# Schematic_new_submission.net
KiCad netlist of a schematic drawn in Altium Designer
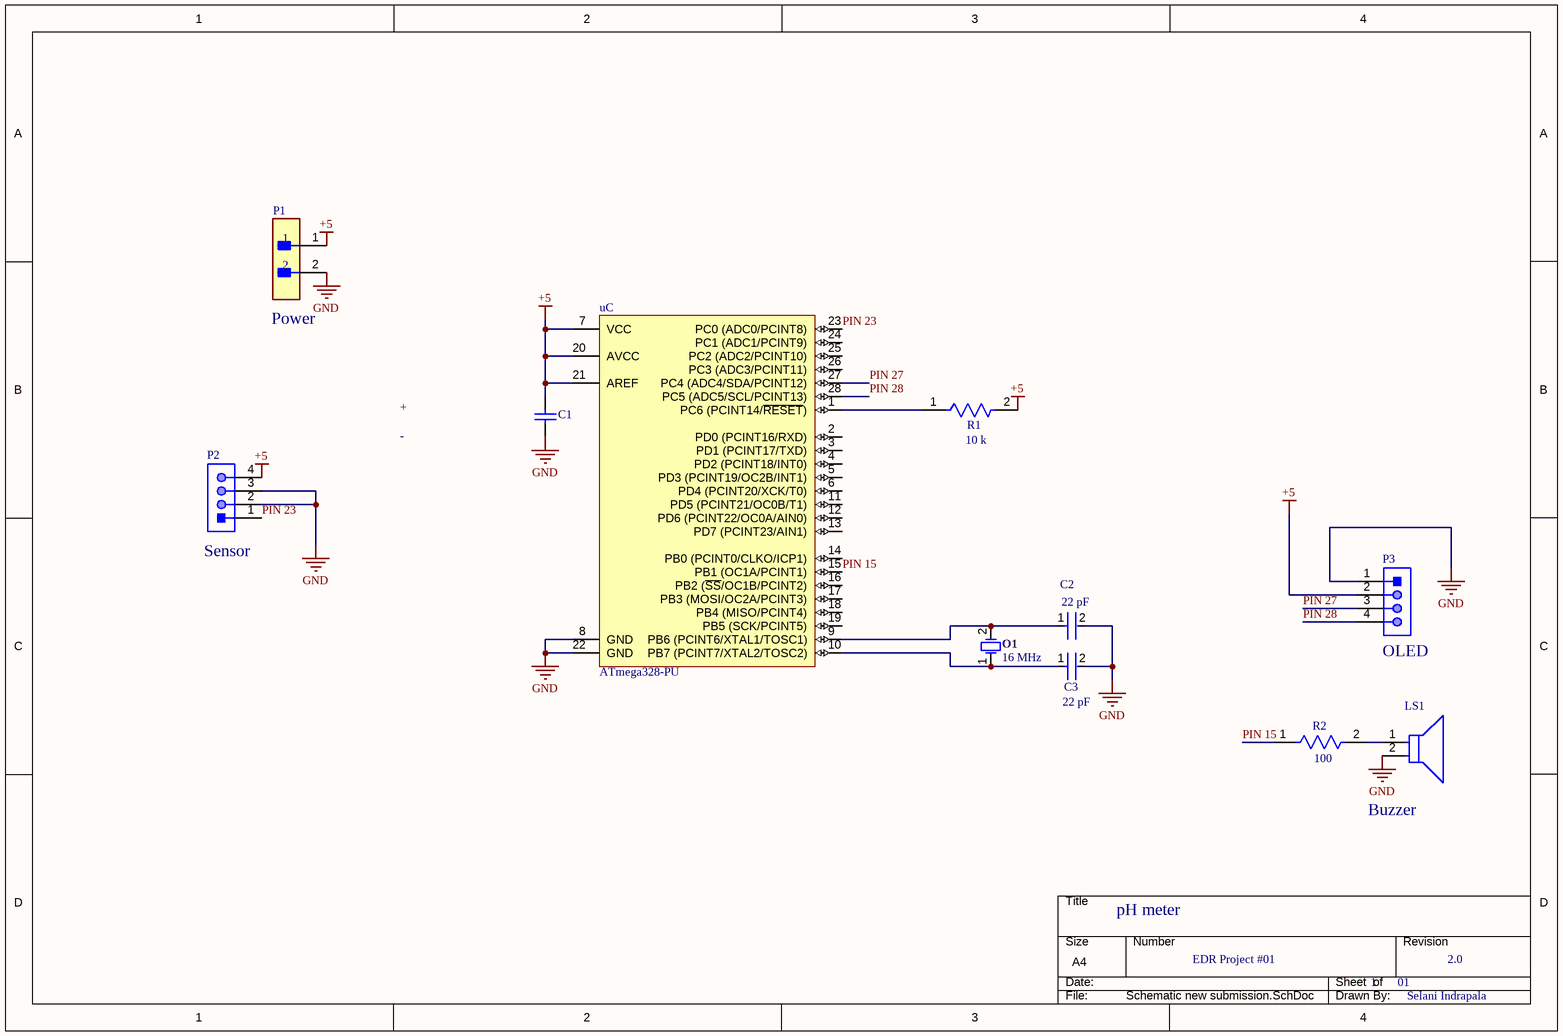
[diagram p0: Schematic new submission.SchDoc]

(export (version "E")
  (design (tool "Eeschema 10.0.6"))
  (components
    (comp (ref "C1")
      (value "MD015E104MAB")
      (footprint "AVX-MD01")
      (description "Ceramic Capacitor, 0.1 uF, +/- 20%, 50 V, -55 to 125 degC, 2-Pin THD (MD01), Bulk")
      (fields (field (name "MANUFACTURER") "AVX"))
      (libsource (lib "Altium Content Vault") (part "CAP-NP-2"))
    )
    (comp (ref "C2")
      (value "RCE5C1H220J0M1H03A")
      (footprint "FP-RCE0K1-MFG")
      (description "Cap Ceramic 22pF 50V C0G ±5% Radial 5mm +125°C Automotive Bulk")
      (fields (field (name "TOLERANCE") "5%"))
      (libsource (lib "Altium Content Vault") (part "b4654b650e69147ec39a6b967a45e02"))
    )
    (comp (ref "C3")
      (value "RCE5C1H220J0M1H03A")
      (footprint "FP-RCE0K1-MFG")
      (description "Cap Ceramic 22pF 50V C0G ±5% Radial 5mm +125°C Automotive Bulk")
      (fields (field (name "TOLERANCE") "5%"))
      (libsource (lib "Altium Content Vault") (part "b4654b650e69147ec39a6b967a45e02"))
    )
    (comp (ref "LS1")
      (value "PS1720P02")
      (footprint "FP-PS1720P02-MFG")
      (description "Audio Buzzer Piezo 3Vo-p Pin Through Hole")
      (fields (field (name "OCTOPART") "https://octopart.com/ps1720p02-tdk-154429"))
      (libsource (lib "Altium Content Vault") (part "5f581d31613f872430949aa526fd155"))
    )
    (comp (ref "O1")
      (value "FOXSLF/160-20")
      (footprint "FOX-FOXSLF160-20")
      (description "Resistance Weld Thru-Hole Crystal, 16 MHz, -20 to 70 degC, 2-Pin THD, RoHS, Bulk")
      (fields (field (name "TOLERANCE") "1%"))
      (libsource (lib "Altium Content Vault") (part "XTAL-1-2-2"))
    )
    (comp (ref "P1")
      (value "M20-9990246")
      (footprint "FP-M20-9990246-MFG")
      (description "CONN HEADER VERT 2POS 2.54MM")
      (fields
        (field (name "OCTOPART") "https://octopart.com/m20-9990246-harwin-2590635")
        (field (name "MANUFACTURER") "Harwin")
      )
      (libsource (lib "Altium Content Vault") (part "3bc925449376181038e59eaffc5286c"))
    )
    (comp (ref "P2")
      (value "Sensor")
      (footprint "61900411121")
      (description "Male Locking Header WR-WTB, THT, Vertical, pitch 2.54 mm, 1 x 4 position")
      (fields
        (field (name "MANUFACTURER") "Wurth Elektronik")
        (field (name "PART NUMBER") "61900411121")
        (field (name "PUBLISHER") "WurthElektronik")
      )
      (libsource (lib "") (part "WE-CN-1P-M-R4_1"))
    )
    (comp (ref "P3")
      (value "OLED")
      (footprint "61900411121")
      (description "Male Locking Header WR-WTB, THT, Vertical, pitch 2.54 mm, 1 x 4 position")
      (fields
        (field (name "MANUFACTURER") "Wurth Elektronik")
        (field (name "PART NUMBER") "61900411121")
        (field (name "PUBLISHER") "WurthElektronik")
      )
      (libsource (lib "Altium Content Vault") (part "WE-CN-1P-M-R4"))
    )
    (comp (ref "R1")
      (value "MBB02070C1002FCT00")
      (footprint "FP-MBB0207-MFG")
      (description "RES 10K OHM 0.6W 1% AXIAL")
      (fields (field (name "TOLERANCE") "1%"))
      (libsource (lib "Altium Content Vault") (part "1029c3af85768c4190bb7ad29bc67b5"))
    )
    (comp (ref "R2")
      (value "RG1005P-101-B-T5")
      (footprint "FP-RG1005-IPC_B")
      (description "Automotive Metal Thin Film Chip Resistor, 0402, 100Ω, 0.1%, 25ppm/°C, 0.0625W, 75V")
      (fields (field (name "TOLERANCE") "0.1%"))
      (libsource (lib "Altium Content Vault") (part "1029c3af85768c4190bb7ad29bc67b5"))
    )
    (comp (ref "uC")
      (value "ATmega328-PU")
      (footprint "28P3")
      (libsource (lib "Altium Content Vault") (part "MC-8B-ATM48-IL28"))
    )
  )
  (nets
    (net (code "1") (name "+5") (class "Default")
      (node (ref "C1") (pin "2") (pinfunction "2_2") (pintype "passive"))
      (node (ref "P1") (pin "1") (pinfunction "1_1") (pintype "passive"))
      (node (ref "P2") (pin "4") (pinfunction "4_4") (pintype "passive"))
      (node (ref "P3") (pin "2") (pinfunction "2_2") (pintype "passive"))
      (node (ref "R1") (pin "2") (pinfunction "2_2") (pintype "passive"))
      (node (ref "uC") (pin "20") (pinfunction "AVCC_20") (pintype "power_in"))
      (node (ref "uC") (pin "21") (pinfunction "AREF_21") (pintype "power_in"))
      (node (ref "uC") (pin "7") (pinfunction "VCC_7") (pintype "power_in"))
    )
    (net (code "2") (name "/PIN 15") (class "Default")
      (node (ref "R2") (pin "1") (pinfunction "1_1") (pintype "passive"))
      (node (ref "uC") (pin "15") (pinfunction "PB1_(OC1A/PCINT1)_15") (pintype "bidirectional"))
    )
    (net (code "3") (name "/PIN 23") (class "Default")
      (node (ref "P2") (pin "1") (pinfunction "1_1") (pintype "passive"))
      (node (ref "uC") (pin "23") (pinfunction "PC0_(ADC0/PCINT8)_23") (pintype "bidirectional"))
    )
    (net (code "4") (name "/PIN 27") (class "Default")
      (node (ref "P3") (pin "3") (pinfunction "3_3") (pintype "passive"))
      (node (ref "uC") (pin "27") (pinfunction "PC4_(ADC4/SDA/PCINT12)_27") (pintype "bidirectional"))
    )
    (net (code "5") (name "/PIN 28") (class "Default")
      (node (ref "P3") (pin "4") (pinfunction "4_4") (pintype "passive"))
      (node (ref "uC") (pin "28") (pinfunction "PC5_(ADC5/SCL/PCINT13)_28") (pintype "bidirectional"))
    )
    (net (code "6") (name "GND") (class "Default")
      (node (ref "C1") (pin "1") (pinfunction "1_1") (pintype "passive"))
      (node (ref "C2") (pin "2") (pinfunction "2_2") (pintype "passive"))
      (node (ref "C3") (pin "2") (pinfunction "2_2") (pintype "passive"))
      (node (ref "LS1") (pin "2") (pinfunction "2_2") (pintype "passive"))
      (node (ref "P1") (pin "2") (pinfunction "2_2") (pintype "passive"))
      (node (ref "P2") (pin "2") (pinfunction "2_2") (pintype "passive"))
      (node (ref "P2") (pin "3") (pinfunction "3_3") (pintype "passive"))
      (node (ref "P3") (pin "1") (pinfunction "1_1") (pintype "passive"))
      (node (ref "uC") (pin "22") (pinfunction "GND_22") (pintype "power_in"))
      (node (ref "uC") (pin "8") (pinfunction "GND_8") (pintype "power_in"))
    )
    (net (code "7") (name "Net-(LS1-Pad1)") (class "Default")
      (node (ref "LS1") (pin "1") (pinfunction "1_1") (pintype "passive"))
      (node (ref "R2") (pin "2") (pinfunction "2_2") (pintype "passive"))
    )
    (net (code "8") (name "Net-(uC-PB6_(PCINT6{slash}XTAL1{slash}TOSC1))") (class "Default")
      (node (ref "C2") (pin "1") (pinfunction "1_1") (pintype "passive"))
      (node (ref "O1") (pin "2") (pinfunction "2_2") (pintype "passive"))
      (node (ref "uC") (pin "9") (pinfunction "PB6_(PCINT6/XTAL1/TOSC1)_9") (pintype "bidirectional"))
    )
    (net (code "9") (name "Net-(uC-PB7_(PCINT7{slash}XTAL2{slash}TOSC2))") (class "Default")
      (node (ref "C3") (pin "1") (pinfunction "1_1") (pintype "passive"))
      (node (ref "O1") (pin "1") (pinfunction "1_1") (pintype "passive"))
      (node (ref "uC") (pin "10") (pinfunction "PB7_(PCINT7/XTAL2/TOSC2)_10") (pintype "bidirectional"))
    )
    (net (code "10") (name "Net-(uC-PC6_(PCINT14{slash}~{RESET}))") (class "Default")
      (node (ref "R1") (pin "1") (pinfunction "1_1") (pintype "passive"))
      (node (ref "uC") (pin "1") (pinfunction "PC6_(PCINT14/~{RESET})_1") (pintype "bidirectional"))
    )
    (net (code "11") (name "unconnected-(uC-PB0_(PCINT0{slash}CLKO{slash}ICP1)-Pad14)") (class "Default")
      (node (ref "uC") (pin "14") (pinfunction "PB0_(PCINT0/CLKO/ICP1)_14") (pintype "bidirectional"))
    )
    (net (code "12") (name "unconnected-(uC-PB2_(~{SS}{slash}OC1B{slash}PCINT2)-Pad16)") (class "Default")
      (node (ref "uC") (pin "16") (pinfunction "PB2_(~{SS}/OC1B/PCINT2)_16") (pintype "bidirectional"))
    )
    (net (code "13") (name "unconnected-(uC-PB3_(MOSI{slash}OC2A{slash}PCINT3)-Pad17)") (class "Default")
      (node (ref "uC") (pin "17") (pinfunction "PB3_(MOSI/OC2A/PCINT3)_17") (pintype "bidirectional"))
    )
    (net (code "14") (name "unconnected-(uC-PB4_(MISO{slash}PCINT4)-Pad18)") (class "Default")
      (node (ref "uC") (pin "18") (pinfunction "PB4_(MISO/PCINT4)_18") (pintype "bidirectional"))
    )
    (net (code "15") (name "unconnected-(uC-PB5_(SCK{slash}PCINT5)-Pad19)") (class "Default")
      (node (ref "uC") (pin "19") (pinfunction "PB5_(SCK/PCINT5)_19") (pintype "bidirectional"))
    )
    (net (code "16") (name "unconnected-(uC-PC1_(ADC1{slash}PCINT9)-Pad24)") (class "Default")
      (node (ref "uC") (pin "24") (pinfunction "PC1_(ADC1/PCINT9)_24") (pintype "bidirectional"))
    )
    (net (code "17") (name "unconnected-(uC-PC2_(ADC2{slash}PCINT10)-Pad25)") (class "Default")
      (node (ref "uC") (pin "25") (pinfunction "PC2_(ADC2/PCINT10)_25") (pintype "bidirectional"))
    )
    (net (code "18") (name "unconnected-(uC-PC3_(ADC3{slash}PCINT11)-Pad26)") (class "Default")
      (node (ref "uC") (pin "26") (pinfunction "PC3_(ADC3/PCINT11)_26") (pintype "bidirectional"))
    )
    (net (code "19") (name "unconnected-(uC-PD0_(PCINT16{slash}RXD)-Pad2)") (class "Default")
      (node (ref "uC") (pin "2") (pinfunction "PD0_(PCINT16/RXD)_2") (pintype "bidirectional"))
    )
    (net (code "20") (name "unconnected-(uC-PD1_(PCINT17{slash}TXD)-Pad3)") (class "Default")
      (node (ref "uC") (pin "3") (pinfunction "PD1_(PCINT17/TXD)_3") (pintype "bidirectional"))
    )
    (net (code "21") (name "unconnected-(uC-PD2_(PCINT18{slash}INT0)-Pad4)") (class "Default")
      (node (ref "uC") (pin "4") (pinfunction "PD2_(PCINT18/INT0)_4") (pintype "bidirectional"))
    )
    (net (code "22") (name "unconnected-(uC-PD3_(PCINT19{slash}OC2B{slash}INT1)-Pad5)") (class "Default")
      (node (ref "uC") (pin "5") (pinfunction "PD3_(PCINT19/OC2B/INT1)_5") (pintype "bidirectional"))
    )
    (net (code "23") (name "unconnected-(uC-PD4_(PCINT20{slash}XCK{slash}T0)-Pad6)") (class "Default")
      (node (ref "uC") (pin "6") (pinfunction "PD4_(PCINT20/XCK/T0)_6") (pintype "bidirectional"))
    )
    (net (code "24") (name "unconnected-(uC-PD5_(PCINT21{slash}OC0B{slash}T1)-Pad11)") (class "Default")
      (node (ref "uC") (pin "11") (pinfunction "PD5_(PCINT21/OC0B/T1)_11") (pintype "bidirectional"))
    )
    (net (code "25") (name "unconnected-(uC-PD6_(PCINT22{slash}OC0A{slash}AIN0)-Pad12)") (class "Default")
      (node (ref "uC") (pin "12") (pinfunction "PD6_(PCINT22/OC0A/AIN0)_12") (pintype "bidirectional"))
    )
    (net (code "26") (name "unconnected-(uC-PD7_(PCINT23{slash}AIN1)-Pad13)") (class "Default")
      (node (ref "uC") (pin "13") (pinfunction "PD7_(PCINT23/AIN1)_13") (pintype "bidirectional"))
    )
  )
)
